# IEPE.net
KiCad netlist of a schematic drawn in Altium Designer
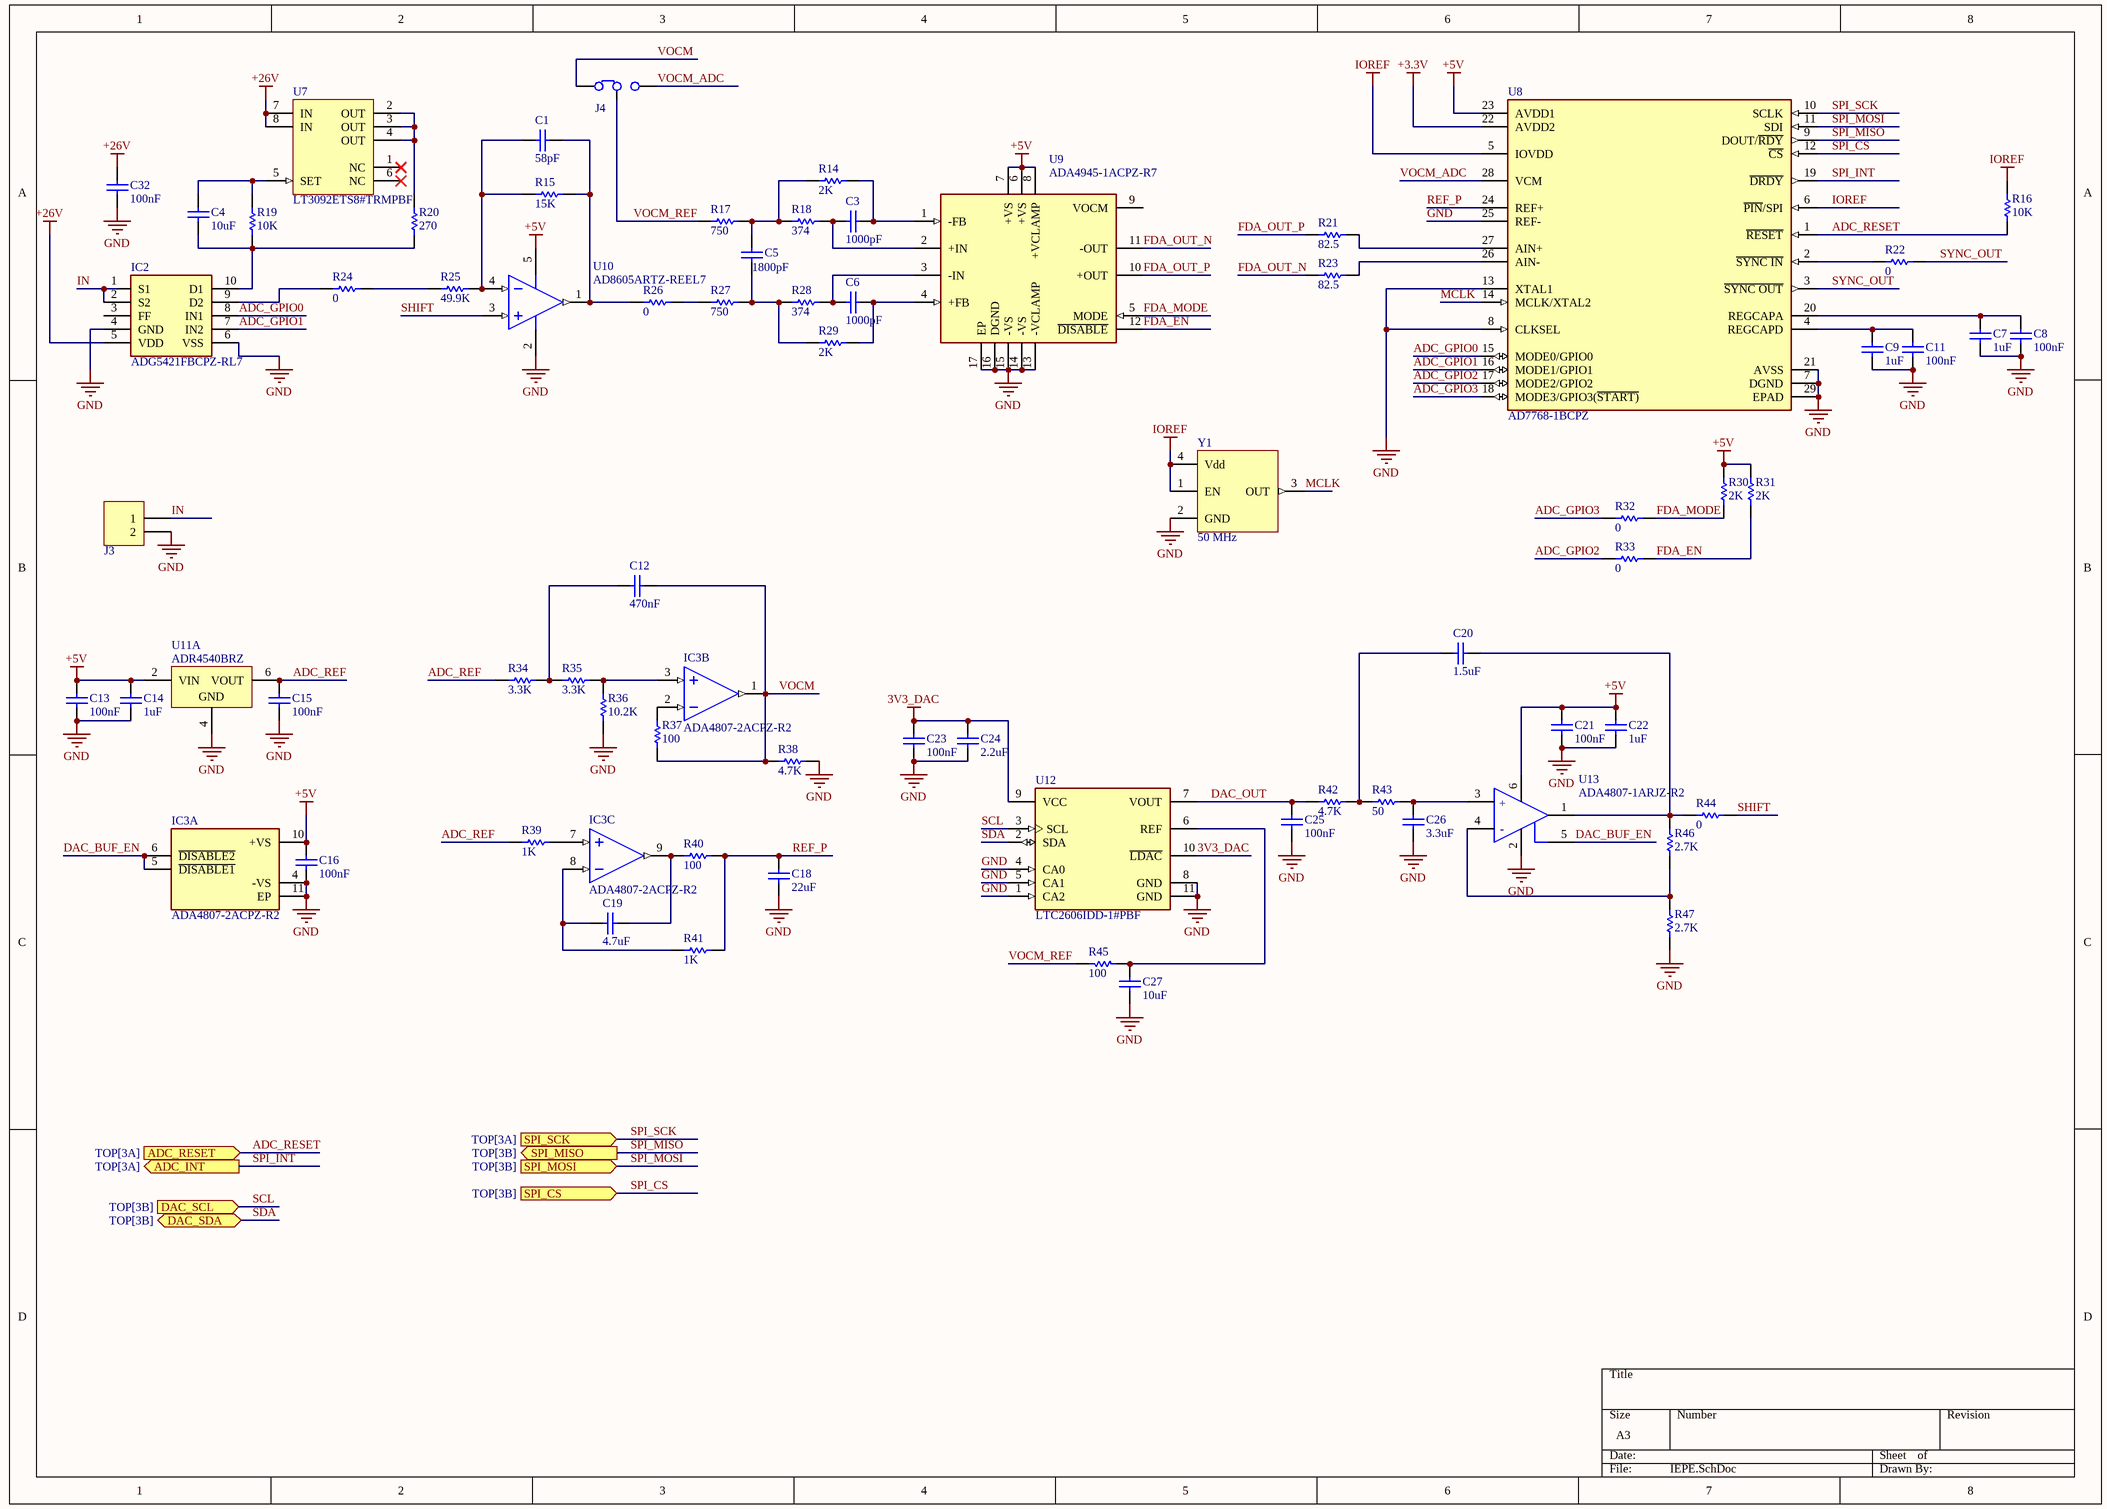
[diagram p0: IEPE.SchDoc]

(export (version "E")
  (design (tool "Eeschema 10.0.6"))
  (components
    (comp (ref "C1")
      (value "58pF")
      (footprint "C603")
      (description "Capacitor")
      (fields (field (name "DESIGNER") "Parsa Malekpour"))
      (libsource (lib "ParsaLibrary") (part "Cap"))
    )
    (comp (ref "C3")
      (value "1000pF")
      (footprint "C603")
      (description "Capacitor")
      (fields (field (name "DESIGNER") "Parsa Malekpour"))
      (libsource (lib "ParsaLibrary") (part "Cap"))
    )
    (comp (ref "C4")
      (value "10uF")
      (footprint "C805")
      (description "Capacitor")
      (fields (field (name "DESIGNER") "Parsa Malekpour"))
      (libsource (lib "ParsaLibrary") (part "Cap"))
    )
    (comp (ref "C5")
      (value "1800pF")
      (footprint "C603")
      (description "Capacitor")
      (fields (field (name "DESIGNER") "Parsa Malekpour"))
      (libsource (lib "ParsaLibrary") (part "Cap"))
    )
    (comp (ref "C6")
      (value "1000pF")
      (footprint "C603")
      (description "Capacitor")
      (fields (field (name "DESIGNER") "Parsa Malekpour"))
      (libsource (lib "ParsaLibrary") (part "Cap"))
    )
    (comp (ref "C7")
      (value "1uF")
      (footprint "C603")
      (description "Capacitor")
      (fields (field (name "DESIGNER") "Parsa Malekpour"))
      (libsource (lib "ParsaLibrary") (part "Cap"))
    )
    (comp (ref "C8")
      (value "100nF")
      (footprint "C603")
      (description "Capacitor")
      (fields (field (name "DESIGNER") "Parsa Malekpour"))
      (libsource (lib "ParsaLibrary") (part "Cap"))
    )
    (comp (ref "C9")
      (value "1uF")
      (footprint "C603")
      (description "Capacitor")
      (fields (field (name "DESIGNER") "Parsa Malekpour"))
      (libsource (lib "ParsaLibrary") (part "Cap"))
    )
    (comp (ref "C11")
      (value "100nF")
      (footprint "C603")
      (description "Capacitor")
      (fields (field (name "DESIGNER") "Parsa Malekpour"))
      (libsource (lib "ParsaLibrary") (part "Cap"))
    )
    (comp (ref "C12")
      (value "470nF")
      (footprint "C603")
      (description "Capacitor")
      (fields (field (name "DESIGNER") "Parsa Malekpour"))
      (libsource (lib "ParsaLibrary") (part "Cap"))
    )
    (comp (ref "C13")
      (value "100nF")
      (footprint "C603")
      (description "Capacitor")
      (fields (field (name "DESIGNER") "Parsa Malekpour"))
      (libsource (lib "ParsaLibrary") (part "Cap"))
    )
    (comp (ref "C14")
      (value "1uF")
      (footprint "C603")
      (description "Capacitor")
      (fields (field (name "DESIGNER") "Parsa Malekpour"))
      (libsource (lib "ParsaLibrary") (part "Cap"))
    )
    (comp (ref "C15")
      (value "100nF")
      (footprint "C603")
      (description "Capacitor")
      (fields (field (name "DESIGNER") "Parsa Malekpour"))
      (libsource (lib "ParsaLibrary") (part "Cap"))
    )
    (comp (ref "C16")
      (value "100nF")
      (footprint "C603")
      (description "Capacitor")
      (fields (field (name "DESIGNER") "Parsa Malekpour"))
      (libsource (lib "ParsaLibrary") (part "Cap"))
    )
    (comp (ref "C18")
      (value "22uF")
      (footprint "C603")
      (description "Capacitor")
      (fields (field (name "DESIGNER") "Parsa Malekpour"))
      (libsource (lib "ParsaLibrary") (part "Cap"))
    )
    (comp (ref "C19")
      (value "4.7uF")
      (footprint "C603")
      (description "Capacitor")
      (fields (field (name "DESIGNER") "Parsa Malekpour"))
      (libsource (lib "ParsaLibrary") (part "Cap"))
    )
    (comp (ref "C20")
      (value "1.5uF")
      (footprint "C603")
      (description "Capacitor")
      (fields (field (name "DESIGNER") "Parsa Malekpour"))
      (libsource (lib "ParsaLibrary") (part "Cap"))
    )
    (comp (ref "C21")
      (value "100nF")
      (footprint "C603")
      (description "Capacitor")
      (fields (field (name "DESIGNER") "Parsa Malekpour"))
      (libsource (lib "ParsaLibrary") (part "Cap"))
    )
    (comp (ref "C22")
      (value "1uF")
      (footprint "C603")
      (description "Capacitor")
      (fields (field (name "DESIGNER") "Parsa Malekpour"))
      (libsource (lib "ParsaLibrary") (part "Cap"))
    )
    (comp (ref "C23")
      (value "100nF")
      (footprint "C603")
      (description "Capacitor")
      (fields (field (name "DESIGNER") "Parsa Malekpour"))
      (libsource (lib "ParsaLibrary") (part "Cap"))
    )
    (comp (ref "C24")
      (value "2.2uF")
      (footprint "C603")
      (description "Capacitor")
      (fields (field (name "DESIGNER") "Parsa Malekpour"))
      (libsource (lib "ParsaLibrary") (part "Cap"))
    )
    (comp (ref "C25")
      (value "100nF")
      (footprint "C603")
      (description "Capacitor")
      (fields (field (name "DESIGNER") "Parsa Malekpour"))
      (libsource (lib "ParsaLibrary") (part "Cap"))
    )
    (comp (ref "C26")
      (value "3.3uF")
      (footprint "C603")
      (description "Capacitor")
      (fields (field (name "DESIGNER") "Parsa Malekpour"))
      (libsource (lib "ParsaLibrary") (part "Cap"))
    )
    (comp (ref "C27")
      (value "10uF")
      (footprint "C603")
      (description "Capacitor")
      (fields (field (name "DESIGNER") "Parsa Malekpour"))
      (libsource (lib "ParsaLibrary") (part "Cap"))
    )
    (comp (ref "C32")
      (value "100nF")
      (footprint "C603")
      (description "Capacitor")
      (fields (field (name "DESIGNER") "Parsa Malekpour"))
      (libsource (lib "ParsaLibrary") (part "Cap"))
    )
    (comp (ref "IC2")
      (value "ADG5421FBCPZ-RL7")
      (footprint "SamacSys:SON50P200X300X80-10N-D")
      (description "Integrated Circuit")
      (fields (field (name "MOUSER PART NUMBER") "584-ADG5421FBCPZ-RL7"))
      (libsource (lib "*") (part "ADG5421FBCPZ-RL7"))
    )
    (comp (ref "IC3")
      (value "ADA4807-2ACPZ-R2")
      (footprint "SON50P300X300X80-11N-D")
      (description "Integrated Circuit")
      (fields (field (name "MOUSER PART NUMBER") "584-ADA4807-2ACPZ-R2"))
      (libsource (lib "1") (part "ADA4807-2ACPZ-R2"))
    )
    (comp (ref "J3") (value "CONN-2") (footprint "SMB-ANT") (libsource (lib "ParsaLibrary") (part "CONN-2")))
    (comp (ref "J4")
      (value "jumper")
      (footprint "jumper-3-SMD")
      (description "Jumper wire")
      (libsource (lib "ParsaLibrary") (part "Triple Jumper"))
    )
    (comp (ref "R14")
      (value "2K")
      (footprint "R0603")
      (description "Resistor")
      (fields (field (name "DESIGNER") "Parsa Malekpour"))
      (libsource (lib "ParsaLibrary") (part "Resistor"))
    )
    (comp (ref "R15")
      (value "15K")
      (footprint "R0603")
      (description "Resistor")
      (fields (field (name "DESIGNER") "Parsa Malekpour"))
      (libsource (lib "ParsaLibrary") (part "Resistor"))
    )
    (comp (ref "R16")
      (value "10K")
      (footprint "R0603")
      (description "Resistor")
      (fields (field (name "DESIGNER") "Parsa Malekpour"))
      (libsource (lib "ParsaLibrary") (part "Resistor"))
    )
    (comp (ref "R17")
      (value "750")
      (footprint "R0603")
      (description "Resistor")
      (fields (field (name "DESIGNER") "Parsa Malekpour"))
      (libsource (lib "ParsaLibrary") (part "Resistor"))
    )
    (comp (ref "R18")
      (value "374")
      (footprint "R0603")
      (description "Resistor")
      (fields (field (name "DESIGNER") "Parsa Malekpour"))
      (libsource (lib "ParsaLibrary") (part "Resistor"))
    )
    (comp (ref "R19")
      (value "10K")
      (footprint "R0603")
      (description "Resistor")
      (fields (field (name "DESIGNER") "Parsa Malekpour"))
      (libsource (lib "ParsaLibrary") (part "Resistor"))
    )
    (comp (ref "R20")
      (value "270")
      (footprint "R0603")
      (description "Resistor")
      (fields (field (name "DESIGNER") "Parsa Malekpour"))
      (libsource (lib "ParsaLibrary") (part "Resistor"))
    )
    (comp (ref "R21")
      (value "82.5")
      (footprint "R0603")
      (description "Resistor")
      (fields (field (name "DESIGNER") "Parsa Malekpour"))
      (libsource (lib "ParsaLibrary") (part "Resistor"))
    )
    (comp (ref "R22")
      (value "0")
      (footprint "R0603")
      (description "Resistor")
      (fields (field (name "DESIGNER") "Parsa Malekpour"))
      (libsource (lib "ParsaLibrary") (part "Resistor"))
    )
    (comp (ref "R23")
      (value "82.5")
      (footprint "R0603")
      (description "Resistor")
      (fields (field (name "DESIGNER") "Parsa Malekpour"))
      (libsource (lib "ParsaLibrary") (part "Resistor"))
    )
    (comp (ref "R24")
      (value "0")
      (footprint "R0603")
      (description "Resistor")
      (fields (field (name "DESIGNER") "Parsa Malekpour"))
      (libsource (lib "ParsaLibrary") (part "Resistor"))
    )
    (comp (ref "R25")
      (value "49.9K")
      (footprint "R0603")
      (description "Resistor")
      (fields (field (name "DESIGNER") "Parsa Malekpour"))
      (libsource (lib "ParsaLibrary") (part "Resistor"))
    )
    (comp (ref "R26")
      (value "0")
      (footprint "R0603")
      (description "Resistor")
      (fields (field (name "DESIGNER") "Parsa Malekpour"))
      (libsource (lib "ParsaLibrary") (part "Resistor"))
    )
    (comp (ref "R27")
      (value "750")
      (footprint "R0603")
      (description "Resistor")
      (fields (field (name "DESIGNER") "Parsa Malekpour"))
      (libsource (lib "ParsaLibrary") (part "Resistor"))
    )
    (comp (ref "R28")
      (value "374")
      (footprint "R0603")
      (description "Resistor")
      (fields (field (name "DESIGNER") "Parsa Malekpour"))
      (libsource (lib "ParsaLibrary") (part "Resistor"))
    )
    (comp (ref "R29")
      (value "2K")
      (footprint "R0603")
      (description "Resistor")
      (fields (field (name "DESIGNER") "Parsa Malekpour"))
      (libsource (lib "ParsaLibrary") (part "Resistor"))
    )
    (comp (ref "R30")
      (value "2K")
      (footprint "R0603")
      (description "Resistor")
      (fields (field (name "DESIGNER") "Parsa Malekpour"))
      (libsource (lib "ParsaLibrary") (part "Resistor"))
    )
    (comp (ref "R31")
      (value "2K")
      (footprint "R0603")
      (description "Resistor")
      (fields (field (name "DESIGNER") "Parsa Malekpour"))
      (libsource (lib "ParsaLibrary") (part "Resistor"))
    )
    (comp (ref "R32")
      (value "0")
      (footprint "R0603")
      (description "Resistor")
      (fields (field (name "DESIGNER") "Parsa Malekpour"))
      (libsource (lib "ParsaLibrary") (part "Resistor"))
    )
    (comp (ref "R33")
      (value "0")
      (footprint "R0603")
      (description "Resistor")
      (fields (field (name "DESIGNER") "Parsa Malekpour"))
      (libsource (lib "ParsaLibrary") (part "Resistor"))
    )
    (comp (ref "R34")
      (value "3.3K")
      (footprint "R0603")
      (description "Resistor")
      (fields (field (name "DESIGNER") "Parsa Malekpour"))
      (libsource (lib "ParsaLibrary") (part "Resistor"))
    )
    (comp (ref "R35")
      (value "3.3K")
      (footprint "R0603")
      (description "Resistor")
      (fields (field (name "DESIGNER") "Parsa Malekpour"))
      (libsource (lib "ParsaLibrary") (part "Resistor"))
    )
    (comp (ref "R36")
      (value "10.2K")
      (footprint "R0603")
      (description "Resistor")
      (fields (field (name "DESIGNER") "Parsa Malekpour"))
      (libsource (lib "ParsaLibrary") (part "Resistor"))
    )
    (comp (ref "R37")
      (value "100")
      (footprint "R0603")
      (description "Resistor")
      (fields (field (name "DESIGNER") "Parsa Malekpour"))
      (libsource (lib "ParsaLibrary") (part "Resistor"))
    )
    (comp (ref "R38")
      (value "4.7K")
      (footprint "R0603")
      (description "Resistor")
      (fields (field (name "DESIGNER") "Parsa Malekpour"))
      (libsource (lib "ParsaLibrary") (part "Resistor"))
    )
    (comp (ref "R39")
      (value "1K")
      (footprint "R0603")
      (description "Resistor")
      (fields (field (name "DESIGNER") "Parsa Malekpour"))
      (libsource (lib "ParsaLibrary") (part "Resistor"))
    )
    (comp (ref "R40")
      (value "100")
      (footprint "R0603")
      (description "Resistor")
      (fields (field (name "DESIGNER") "Parsa Malekpour"))
      (libsource (lib "ParsaLibrary") (part "Resistor"))
    )
    (comp (ref "R41")
      (value "1K")
      (footprint "R0603")
      (description "Resistor")
      (fields (field (name "DESIGNER") "Parsa Malekpour"))
      (libsource (lib "ParsaLibrary") (part "Resistor"))
    )
    (comp (ref "R42")
      (value "4.7K")
      (footprint "R0603")
      (description "Resistor")
      (fields (field (name "DESIGNER") "Parsa Malekpour"))
      (libsource (lib "ParsaLibrary") (part "Resistor"))
    )
    (comp (ref "R43")
      (value "50")
      (footprint "R0603")
      (description "Resistor")
      (fields (field (name "DESIGNER") "Parsa Malekpour"))
      (libsource (lib "ParsaLibrary") (part "Resistor"))
    )
    (comp (ref "R44")
      (value "0")
      (footprint "R0603")
      (description "Resistor")
      (fields (field (name "DESIGNER") "Parsa Malekpour"))
      (libsource (lib "ParsaLibrary") (part "Resistor"))
    )
    (comp (ref "R45")
      (value "100")
      (footprint "R0603")
      (description "Resistor")
      (fields (field (name "DESIGNER") "Parsa Malekpour"))
      (libsource (lib "ParsaLibrary") (part "Resistor"))
    )
    (comp (ref "R46")
      (value "2.7K")
      (footprint "R0603")
      (description "Resistor")
      (fields (field (name "DESIGNER") "Parsa Malekpour"))
      (libsource (lib "ParsaLibrary") (part "Resistor"))
    )
    (comp (ref "R47")
      (value "2.7K")
      (footprint "R0603")
      (description "Resistor")
      (fields (field (name "DESIGNER") "Parsa Malekpour"))
      (libsource (lib "ParsaLibrary") (part "Resistor"))
    )
    (comp (ref "U7")
      (value "LT3092ETS8#TRMPBF")
      (footprint "SOT65P280X100-8N")
      (fields (field (name "MANUFACTURER") "Linear Technology"))
      (libsource (lib "SamacSys") (part "LT-LT3092-TS8-8"))
    )
    (comp (ref "U8")
      (value "AD7768-1BCPZ")
      (footprint "FP-CP-28-12-IPC_C")
      (description "IC ADC 24BIT SIGMA-DELTA 28LFCSP")
      (libsource (lib "Altium Content Vault") (part "6bcfa4bee2ba14552dcdb65def92038"))
    )
    (comp (ref "U9")
      (value "ADA4945-1ACPZ-R7")
      (footprint "FP-CP-16-22-IPC_C")
      (description "IC ADC DRIVER 16LFCSP")
      (libsource (lib "ParsaLibrary") (part "ADA4945-1ACPZ-R7"))
    )
    (comp (ref "U10")
      (value "AD8605ARTZ-REEL7")
      (footprint "SOT95P280X145-5N")
      (fields (field (name "MANUFACTURER") "Analog Devices") (field (name "GENERIC PART NUMBER") "AD8605"))
      (libsource (lib "SamacSys") (part "ADI-ADxxxx-X-5"))
    )
    (comp (ref "U11")
      (value "ADR4540BRZ")
      (footprint "SOIC-8N")
      (fields (field (name "MANUFACTURER") "Analog Devices"))
      (libsource (lib "SamacSys") (part "ADI-ADR45xx-R-8"))
    )
    (comp (ref "U12")
      (value "LTC2606IDD-1#PBF")
      (footprint "FP-DD-10-05-08-1699-IPC_C")
      (description "IC DAC 16BIT V-OUT 10DFN")
      (libsource (lib "Altium Content Vault") (part "0d41aa5bbc5989ae32548436e883e6b"))
    )
    (comp (ref "U13")
      (value "ADA4807-1ARJZ-R2")
      (footprint "FP-RJ-6-IPC_A")
      (description "IC OPAMP VFB 1 CIRCUIT SOT23-6")
      (libsource (lib "Altium Content Vault") (part "0cc169e61f44c0172c2773b4ba3b2c6"))
    )
    (comp (ref "Y1")
      (value "50 MHz")
      (footprint "OSC3225")
      (description "OSCILLATOR")
      (fields (field (name "FREQUENCY") "50 MHz"))
      (libsource (lib "ParsaLibrary") (part "OSCILLATOR"))
    )
  )
  (nets
    (net (code "1") (name "+3.3V") (class "Default")
      (node (ref "U8") (pin "22") (pinfunction "AVDD2_22") (pintype "power_in"))
    )
    (net (code "2") (name "+5V") (class "Default")
      (node (ref "C13") (pin "1") (pinfunction "1_1") (pintype "passive"))
      (node (ref "C14") (pin "1") (pinfunction "1_1") (pintype "passive"))
      (node (ref "C16") (pin "1") (pinfunction "1_1") (pintype "passive"))
      (node (ref "C21") (pin "1") (pinfunction "1_1") (pintype "passive"))
      (node (ref "C22") (pin "1") (pinfunction "1_1") (pintype "passive"))
      (node (ref "IC3") (pin "10") (pinfunction "+VS_10") (pintype "passive"))
      (node (ref "R30") (pin "1") (pinfunction "1_1") (pintype "passive"))
      (node (ref "R31") (pin "1") (pinfunction "1_1") (pintype "passive"))
      (node (ref "U10") (pin "5") (pinfunction "+V_5") (pintype "power_in"))
      (node (ref "U11") (pin "2") (pinfunction "VIN_2") (pintype "power_in"))
      (node (ref "U13") (pin "6") (pinfunction "+VS_6") (pintype "power_in"))
      (node (ref "U8") (pin "23") (pinfunction "AVDD1_23") (pintype "power_in"))
      (node (ref "U9") (pin "6") (pinfunction "+VS_6") (pintype "power_in"))
      (node (ref "U9") (pin "7") (pinfunction "+VS_7") (pintype "power_in"))
      (node (ref "U9") (pin "8") (pinfunction "+VCLAMP_8") (pintype "power_in"))
    )
    (net (code "3") (name "+26V") (class "Default")
      (node (ref "C32") (pin "1") (pinfunction "1_1") (pintype "passive"))
      (node (ref "IC2") (pin "5") (pinfunction "VDD_5") (pintype "passive"))
      (node (ref "U7") (pin "7") (pinfunction "IN_7") (pintype "power_in"))
      (node (ref "U7") (pin "8") (pinfunction "IN_8") (pintype "power_in"))
    )
    (net (code "4") (name "/ADC_GPIO0") (class "Default")
      (node (ref "IC2") (pin "8") (pinfunction "IN1_8") (pintype "passive"))
      (node (ref "U8") (pin "15") (pinfunction "MODE0/GPIO0_15") (pintype "bidirectional"))
    )
    (net (code "5") (name "/ADC_GPIO1") (class "Default")
      (node (ref "IC2") (pin "7") (pinfunction "IN2_7") (pintype "passive"))
      (node (ref "U8") (pin "16") (pinfunction "MODE1/GPIO1_16") (pintype "bidirectional"))
    )
    (net (code "6") (name "/ADC_GPIO2") (class "Default")
      (node (ref "R33") (pin "2") (pinfunction "2_2") (pintype "passive"))
      (node (ref "U8") (pin "17") (pinfunction "MODE2/GPIO2_17") (pintype "bidirectional"))
    )
    (net (code "7") (name "/ADC_GPIO3") (class "Default")
      (node (ref "R32") (pin "2") (pinfunction "2_2") (pintype "passive"))
      (node (ref "U8") (pin "18") (pinfunction "MODE3/GPIO3(~{START)}_18") (pintype "bidirectional"))
    )
    (net (code "8") (name "/ADC_REF") (class "Default")
      (node (ref "C15") (pin "1") (pinfunction "1_1") (pintype "passive"))
      (node (ref "R34") (pin "2") (pinfunction "2_2") (pintype "passive"))
      (node (ref "R39") (pin "1") (pinfunction "1_1") (pintype "passive"))
      (node (ref "U11") (pin "6") (pinfunction "VOUT_6") (pintype "power_in"))
    )
    (net (code "9") (name "/ADC_RESET") (class "Default")
      (node (ref "R16") (pin "2") (pinfunction "2_2") (pintype "passive"))
      (node (ref "U8") (pin "1") (pinfunction "~{RESET}_1") (pintype "input"))
    )
    (net (code "10") (name "/DAC_BUF_EN") (class "Default")
      (node (ref "IC3") (pin "5") (pinfunction "~{DISABLE1}_5") (pintype "passive"))
      (node (ref "IC3") (pin "6") (pinfunction "~{DISABLE2}_6") (pintype "passive"))
      (node (ref "U13") (pin "5") (pinfunction "~{DISABLE}_5") (pintype "passive"))
    )
    (net (code "11") (name "/DAC_OUT") (class "Default")
      (node (ref "C25") (pin "1") (pinfunction "1_1") (pintype "passive"))
      (node (ref "R42") (pin "1") (pinfunction "1_1") (pintype "passive"))
      (node (ref "U12") (pin "7") (pinfunction "VOUT_7") (pintype "passive"))
    )
    (net (code "12") (name "/FDA_EN") (class "Default")
      (node (ref "R31") (pin "2") (pinfunction "2_2") (pintype "passive"))
      (node (ref "R33") (pin "1") (pinfunction "1_1") (pintype "passive"))
      (node (ref "U9") (pin "12") (pinfunction "~{DISABLE}_12") (pintype "passive"))
    )
    (net (code "13") (name "/FDA_MODE") (class "Default")
      (node (ref "R30") (pin "2") (pinfunction "2_2") (pintype "passive"))
      (node (ref "R32") (pin "1") (pinfunction "1_1") (pintype "passive"))
      (node (ref "U9") (pin "5") (pinfunction "MODE_5") (pintype "input"))
    )
    (net (code "14") (name "/FDA_OUT_N") (class "Default")
      (node (ref "R23") (pin "2") (pinfunction "2_2") (pintype "passive"))
      (node (ref "U9") (pin "11") (pinfunction "-OUT_11") (pintype "passive"))
    )
    (net (code "15") (name "/FDA_OUT_P") (class "Default")
      (node (ref "R21") (pin "2") (pinfunction "2_2") (pintype "passive"))
      (node (ref "U9") (pin "10") (pinfunction "+OUT_10") (pintype "passive"))
    )
    (net (code "16") (name "/IN") (class "Default")
      (node (ref "IC2") (pin "1") (pinfunction "S1_1") (pintype "passive"))
      (node (ref "IC2") (pin "2") (pinfunction "S2_2") (pintype "passive"))
      (node (ref "J3") (pin "1") (pinfunction "1_1") (pintype "passive"))
    )
    (net (code "17") (name "/MCLK") (class "Default")
      (node (ref "U8") (pin "14") (pinfunction "MCLK/XTAL2_14") (pintype "input"))
      (node (ref "Y1") (pin "3") (pinfunction "OUT_3") (pintype "output"))
    )
    (net (code "18") (name "/REF_P") (class "Default")
      (node (ref "C18") (pin "1") (pinfunction "1_1") (pintype "passive"))
      (node (ref "R40") (pin "2") (pinfunction "2_2") (pintype "passive"))
      (node (ref "R41") (pin "2") (pinfunction "2_2") (pintype "passive"))
      (node (ref "U8") (pin "24") (pinfunction "REF+_24") (pintype "passive"))
    )
    (net (code "19") (name "/SCL") (class "Default")
      (node (ref "U12") (pin "3") (pinfunction "SCL_3") (pintype "input"))
    )
    (net (code "20") (name "/SDA") (class "Default")
      (node (ref "U12") (pin "2") (pinfunction "SDA_2") (pintype "bidirectional"))
    )
    (net (code "21") (name "/SHIFT") (class "Default")
      (node (ref "R44") (pin "2") (pinfunction "2_2") (pintype "passive"))
      (node (ref "U10") (pin "3") (pinfunction "+IN_3") (pintype "input"))
    )
    (net (code "22") (name "/SPI_CS") (class "Default")
      (node (ref "U8") (pin "12") (pinfunction "~{CS}_12") (pintype "input"))
    )
    (net (code "23") (name "/SPI_INT") (class "Default")
      (node (ref "U8") (pin "19") (pinfunction "~{DRDY}_19") (pintype "output"))
    )
    (net (code "24") (name "/SPI_MISO") (class "Default")
      (node (ref "U8") (pin "9") (pinfunction "DOUT/~{RDY}_9") (pintype "output"))
    )
    (net (code "25") (name "/SPI_MOSI") (class "Default")
      (node (ref "U8") (pin "11") (pinfunction "SDI_11") (pintype "input"))
    )
    (net (code "26") (name "/SPI_SCK") (class "Default")
      (node (ref "U8") (pin "10") (pinfunction "SCLK_10") (pintype "input"))
    )
    (net (code "27") (name "/SYNC_OUT") (class "Default")
      (node (ref "R22") (pin "1") (pinfunction "1_1") (pintype "passive"))
      (node (ref "U8") (pin "3") (pinfunction "~{SYNC_OUT}_3") (pintype "output"))
    )
    (net (code "28") (name "/VOCM") (class "Default")
      (node (ref "C12") (pin "1") (pinfunction "1_1") (pintype "passive"))
      (node (ref "IC3") (pin "1") (pinfunction "VOUT_1") (pintype "output"))
      (node (ref "J4") (pin "1") (pinfunction "C1_1") (pintype "passive"))
      (node (ref "R37") (pin "2") (pinfunction "2_2") (pintype "passive"))
      (node (ref "R38") (pin "1") (pinfunction "1_1") (pintype "passive"))
    )
    (net (code "29") (name "/VOCM_ADC") (class "Default")
      (node (ref "J4") (pin "3") (pinfunction "C3_3") (pintype "passive"))
      (node (ref "U8") (pin "28") (pinfunction "VCM_28") (pintype "passive"))
    )
    (net (code "30") (name "/VOCM_REF") (class "Default")
      (node (ref "J4") (pin "2") (pinfunction "C2_2") (pintype "passive"))
      (node (ref "R17") (pin "2") (pinfunction "2_2") (pintype "passive"))
      (node (ref "R45") (pin "2") (pinfunction "2_2") (pintype "passive"))
    )
    (net (code "31") (name "3V3_DAC") (class "Default")
      (node (ref "C23") (pin "1") (pinfunction "1_1") (pintype "passive"))
      (node (ref "C24") (pin "1") (pinfunction "1_1") (pintype "passive"))
      (node (ref "U12") (pin "10") (pinfunction "~{LDAC}_10") (pintype "passive"))
      (node (ref "U12") (pin "9") (pinfunction "VCC_9") (pintype "power_in"))
    )
    (net (code "32") (name "GND") (class "Default")
      (node (ref "C11") (pin "2") (pinfunction "2_2") (pintype "passive"))
      (node (ref "C13") (pin "2") (pinfunction "2_2") (pintype "passive"))
      (node (ref "C14") (pin "2") (pinfunction "2_2") (pintype "passive"))
      (node (ref "C15") (pin "2") (pinfunction "2_2") (pintype "passive"))
      (node (ref "C16") (pin "2") (pinfunction "2_2") (pintype "passive"))
      (node (ref "C18") (pin "2") (pinfunction "2_2") (pintype "passive"))
      (node (ref "C21") (pin "2") (pinfunction "2_2") (pintype "passive"))
      (node (ref "C22") (pin "2") (pinfunction "2_2") (pintype "passive"))
      (node (ref "C23") (pin "2") (pinfunction "2_2") (pintype "passive"))
      (node (ref "C24") (pin "2") (pinfunction "2_2") (pintype "passive"))
      (node (ref "C25") (pin "2") (pinfunction "2_2") (pintype "passive"))
      (node (ref "C26") (pin "2") (pinfunction "2_2") (pintype "passive"))
      (node (ref "C27") (pin "2") (pinfunction "2_2") (pintype "passive"))
      (node (ref "C32") (pin "2") (pinfunction "2_2") (pintype "passive"))
      (node (ref "C7") (pin "2") (pinfunction "2_2") (pintype "passive"))
      (node (ref "C8") (pin "2") (pinfunction "2_2") (pintype "passive"))
      (node (ref "C9") (pin "2") (pinfunction "2_2") (pintype "passive"))
      (node (ref "IC2") (pin "4") (pinfunction "GND_4") (pintype "passive"))
      (node (ref "IC2") (pin "6") (pinfunction "VSS_6") (pintype "passive"))
      (node (ref "IC3") (pin "11") (pinfunction "EP_11") (pintype "passive"))
      (node (ref "IC3") (pin "4") (pinfunction "-VS_4") (pintype "passive"))
      (node (ref "J3") (pin "2") (pinfunction "2_2") (pintype "passive"))
      (node (ref "R36") (pin "2") (pinfunction "2_2") (pintype "passive"))
      (node (ref "R38") (pin "2") (pinfunction "2_2") (pintype "passive"))
      (node (ref "R47") (pin "1") (pinfunction "1_1") (pintype "passive"))
      (node (ref "U10") (pin "2") (pinfunction "-V_2") (pintype "power_in"))
      (node (ref "U11") (pin "4") (pinfunction "GND_4") (pintype "power_in"))
      (node (ref "U12") (pin "1") (pinfunction "CA2_1") (pintype "input"))
      (node (ref "U12") (pin "11") (pinfunction "GND_11") (pintype "power_in"))
      (node (ref "U12") (pin "4") (pinfunction "CA0_4") (pintype "input"))
      (node (ref "U12") (pin "5") (pinfunction "CA1_5") (pintype "input"))
      (node (ref "U12") (pin "8") (pinfunction "GND_8") (pintype "power_in"))
      (node (ref "U13") (pin "2") (pinfunction "-VS_2") (pintype "power_in"))
      (node (ref "U8") (pin "13") (pinfunction "XTAL1_13") (pintype "passive"))
      (node (ref "U8") (pin "21") (pinfunction "AVSS_21") (pintype "power_in"))
      (node (ref "U8") (pin "25") (pinfunction "REF-_25") (pintype "passive"))
      (node (ref "U8") (pin "29") (pinfunction "EPAD_29") (pintype "power_in"))
      (node (ref "U8") (pin "7") (pinfunction "DGND_7") (pintype "power_in"))
      (node (ref "U8") (pin "8") (pinfunction "CLKSEL_8") (pintype "input"))
      (node (ref "U9") (pin "13") (pinfunction "-VCLAMP_13") (pintype "power_in"))
      (node (ref "U9") (pin "14") (pinfunction "-VS_14") (pintype "power_in"))
      (node (ref "U9") (pin "15") (pinfunction "-VS_15") (pintype "power_in"))
      (node (ref "U9") (pin "16") (pinfunction "DGND_16") (pintype "power_in"))
      (node (ref "U9") (pin "17") (pinfunction "EP_17") (pintype "passive"))
      (node (ref "Y1") (pin "2") (pinfunction "GND_2") (pintype "passive"))
    )
    (net (code "33") (name "IOREF") (class "Default")
      (node (ref "R16") (pin "1") (pinfunction "1_1") (pintype "passive"))
      (node (ref "U8") (pin "5") (pinfunction "IOVDD_5") (pintype "power_in"))
      (node (ref "U8") (pin "6") (pinfunction "~{PIN}/SPI_6") (pintype "input"))
      (node (ref "Y1") (pin "1") (pinfunction "EN_1") (pintype "passive"))
      (node (ref "Y1") (pin "4") (pinfunction "Vdd_4") (pintype "passive"))
    )
    (net (code "34") (name "Net-(C5-Pad1)") (class "Default")
      (node (ref "C5") (pin "1") (pinfunction "1_1") (pintype "passive"))
      (node (ref "R14") (pin "2") (pinfunction "2_2") (pintype "passive"))
      (node (ref "R17") (pin "1") (pinfunction "1_1") (pintype "passive"))
      (node (ref "R18") (pin "2") (pinfunction "2_2") (pintype "passive"))
    )
    (net (code "35") (name "Net-(C5-Pad2)") (class "Default")
      (node (ref "C5") (pin "2") (pinfunction "2_2") (pintype "passive"))
      (node (ref "R27") (pin "1") (pinfunction "1_1") (pintype "passive"))
      (node (ref "R28") (pin "2") (pinfunction "2_2") (pintype "passive"))
      (node (ref "R29") (pin "2") (pinfunction "2_2") (pintype "passive"))
    )
    (net (code "36") (name "Net-(C12-Pad2)") (class "Default")
      (node (ref "C12") (pin "2") (pinfunction "2_2") (pintype "passive"))
      (node (ref "R34") (pin "1") (pinfunction "1_1") (pintype "passive"))
      (node (ref "R35") (pin "2") (pinfunction "2_2") (pintype "passive"))
    )
    (net (code "37") (name "Net-(C20-Pad1)") (class "Default")
      (node (ref "C20") (pin "1") (pinfunction "1_1") (pintype "passive"))
      (node (ref "R42") (pin "2") (pinfunction "2_2") (pintype "passive"))
      (node (ref "R43") (pin "1") (pinfunction "1_1") (pintype "passive"))
    )
    (net (code "38") (name "Net-(IC2-D1)") (class "Default")
      (node (ref "C4") (pin "1") (pinfunction "1_1") (pintype "passive"))
      (node (ref "IC2") (pin "10") (pinfunction "D1_10") (pintype "passive"))
      (node (ref "R19") (pin "1") (pinfunction "1_1") (pintype "passive"))
      (node (ref "R20") (pin "1") (pinfunction "1_1") (pintype "passive"))
    )
    (net (code "39") (name "Net-(IC2-D2)") (class "Default")
      (node (ref "IC2") (pin "9") (pinfunction "D2_9") (pintype "passive"))
      (node (ref "R24") (pin "2") (pinfunction "2_2") (pintype "passive"))
    )
    (net (code "40") (name "Net-(IC3B-+IN1)") (class "Default")
      (node (ref "IC3") (pin "3") (pinfunction "+IN1_3") (pintype "input"))
      (node (ref "R35") (pin "1") (pinfunction "1_1") (pintype "passive"))
      (node (ref "R36") (pin "1") (pinfunction "1_1") (pintype "passive"))
    )
    (net (code "41") (name "Net-(IC3B--IN1)") (class "Default")
      (node (ref "IC3") (pin "2") (pinfunction "-IN1_2") (pintype "input"))
      (node (ref "R37") (pin "1") (pinfunction "1_1") (pintype "passive"))
    )
    (net (code "42") (name "Net-(IC3C-+IN2)") (class "Default")
      (node (ref "IC3") (pin "7") (pinfunction "+IN2_7") (pintype "input"))
      (node (ref "R39") (pin "2") (pinfunction "2_2") (pintype "passive"))
    )
    (net (code "43") (name "Net-(IC3C--IN2)") (class "Default")
      (node (ref "C19") (pin "2") (pinfunction "2_2") (pintype "passive"))
      (node (ref "IC3") (pin "8") (pinfunction "-IN2_8") (pintype "input"))
      (node (ref "R41") (pin "1") (pinfunction "1_1") (pintype "passive"))
    )
    (net (code "44") (name "Net-(IC3C-VOUT2)") (class "Default")
      (node (ref "C19") (pin "1") (pinfunction "1_1") (pintype "passive"))
      (node (ref "IC3") (pin "9") (pinfunction "VOUT2_9") (pintype "output"))
      (node (ref "R40") (pin "1") (pinfunction "1_1") (pintype "passive"))
    )
    (net (code "45") (name "Net-(R20-Pad2)") (class "Default")
      (node (ref "R20") (pin "2") (pinfunction "2_2") (pintype "passive"))
      (node (ref "U7") (pin "2") (pinfunction "OUT_2") (pintype "power_in"))
      (node (ref "U7") (pin "3") (pinfunction "OUT_3") (pintype "power_in"))
      (node (ref "U7") (pin "4") (pinfunction "OUT_4") (pintype "power_in"))
    )
    (net (code "46") (name "Net-(R24-Pad1)") (class "Default")
      (node (ref "R24") (pin "1") (pinfunction "1_1") (pintype "passive"))
      (node (ref "R25") (pin "2") (pinfunction "2_2") (pintype "passive"))
    )
    (net (code "47") (name "Net-(R26-Pad1)") (class "Default")
      (node (ref "R26") (pin "1") (pinfunction "1_1") (pintype "passive"))
      (node (ref "R27") (pin "2") (pinfunction "2_2") (pintype "passive"))
    )
    (net (code "48") (name "Net-(U7-SET)") (class "Default")
      (node (ref "C4") (pin "2") (pinfunction "2_2") (pintype "passive"))
      (node (ref "R19") (pin "2") (pinfunction "2_2") (pintype "passive"))
      (node (ref "U7") (pin "5") (pinfunction "SET_5") (pintype "input"))
    )
    (net (code "49") (name "Net-(U8-AIN+)") (class "Default")
      (node (ref "R21") (pin "1") (pinfunction "1_1") (pintype "passive"))
      (node (ref "U8") (pin "27") (pinfunction "AIN+_27") (pintype "passive"))
    )
    (net (code "50") (name "Net-(U8-AIN-)") (class "Default")
      (node (ref "R23") (pin "1") (pinfunction "1_1") (pintype "passive"))
      (node (ref "U8") (pin "26") (pinfunction "AIN-_26") (pintype "passive"))
    )
    (net (code "51") (name "Net-(U8-REGCAPA)") (class "Default")
      (node (ref "C7") (pin "1") (pinfunction "1_1") (pintype "passive"))
      (node (ref "C8") (pin "1") (pinfunction "1_1") (pintype "passive"))
      (node (ref "U8") (pin "20") (pinfunction "REGCAPA_20") (pintype "passive"))
    )
    (net (code "52") (name "Net-(U8-REGCAPD)") (class "Default")
      (node (ref "C11") (pin "1") (pinfunction "1_1") (pintype "passive"))
      (node (ref "C9") (pin "1") (pinfunction "1_1") (pintype "passive"))
      (node (ref "U8") (pin "4") (pinfunction "REGCAPD_4") (pintype "passive"))
    )
    (net (code "53") (name "Net-(U8-~{SYNC_IN})") (class "Default")
      (node (ref "R22") (pin "2") (pinfunction "2_2") (pintype "passive"))
      (node (ref "U8") (pin "2") (pinfunction "~{SYNC_IN}_2") (pintype "input"))
    )
    (net (code "54") (name "Net-(U9-+FB)") (class "Default")
      (node (ref "C6") (pin "2") (pinfunction "2_2") (pintype "passive"))
      (node (ref "R29") (pin "1") (pinfunction "1_1") (pintype "passive"))
      (node (ref "U9") (pin "4") (pinfunction "+FB_4") (pintype "input"))
    )
    (net (code "55") (name "Net-(U9-+IN)") (class "Default")
      (node (ref "C3") (pin "1") (pinfunction "1_1") (pintype "passive"))
      (node (ref "R18") (pin "1") (pinfunction "1_1") (pintype "passive"))
      (node (ref "U9") (pin "2") (pinfunction "+IN_2") (pintype "power_in"))
    )
    (net (code "56") (name "Net-(U9--FB)") (class "Default")
      (node (ref "C3") (pin "2") (pinfunction "2_2") (pintype "passive"))
      (node (ref "R14") (pin "1") (pinfunction "1_1") (pintype "passive"))
      (node (ref "U9") (pin "1") (pinfunction "-FB_1") (pintype "input"))
    )
    (net (code "57") (name "Net-(U9--IN)") (class "Default")
      (node (ref "C6") (pin "1") (pinfunction "1_1") (pintype "passive"))
      (node (ref "R28") (pin "1") (pinfunction "1_1") (pintype "passive"))
      (node (ref "U9") (pin "3") (pinfunction "-IN_3") (pintype "power_in"))
    )
    (net (code "58") (name "Net-(U10--IN)") (class "Default")
      (node (ref "C1") (pin "2") (pinfunction "2_2") (pintype "passive"))
      (node (ref "R15") (pin "2") (pinfunction "2_2") (pintype "passive"))
      (node (ref "R25") (pin "1") (pinfunction "1_1") (pintype "passive"))
      (node (ref "U10") (pin "4") (pinfunction "-IN_4") (pintype "input"))
    )
    (net (code "59") (name "Net-(U10-OUT)") (class "Default")
      (node (ref "C1") (pin "1") (pinfunction "1_1") (pintype "passive"))
      (node (ref "R15") (pin "1") (pinfunction "1_1") (pintype "passive"))
      (node (ref "R26") (pin "2") (pinfunction "2_2") (pintype "passive"))
      (node (ref "U10") (pin "1") (pinfunction "OUT_1") (pintype "output"))
    )
    (net (code "60") (name "Net-(U12-REF)") (class "Default")
      (node (ref "C27") (pin "1") (pinfunction "1_1") (pintype "passive"))
      (node (ref "R45") (pin "1") (pinfunction "1_1") (pintype "passive"))
      (node (ref "U12") (pin "6") (pinfunction "REF_6") (pintype "passive"))
    )
    (net (code "61") (name "Net-(U13-+IN)") (class "Default")
      (node (ref "C26") (pin "1") (pinfunction "1_1") (pintype "passive"))
      (node (ref "R43") (pin "2") (pinfunction "2_2") (pintype "passive"))
      (node (ref "U13") (pin "3") (pinfunction "+IN_3") (pintype "tri_state"))
    )
    (net (code "62") (name "Net-(U13--IN)") (class "Default")
      (node (ref "R46") (pin "1") (pinfunction "1_1") (pintype "passive"))
      (node (ref "R47") (pin "2") (pinfunction "2_2") (pintype "passive"))
      (node (ref "U13") (pin "4") (pinfunction "-IN_4") (pintype "tri_state"))
    )
    (net (code "63") (name "Net-(U13-VOUT)") (class "Default")
      (node (ref "C20") (pin "2") (pinfunction "2_2") (pintype "passive"))
      (node (ref "R44") (pin "1") (pinfunction "1_1") (pintype "passive"))
      (node (ref "R46") (pin "2") (pinfunction "2_2") (pintype "passive"))
      (node (ref "U13") (pin "1") (pinfunction "VOUT_1") (pintype "passive"))
    )
    (net (code "64") (name "unconnected-(IC2-FF-Pad3)") (class "Default")
      (node (ref "IC2") (pin "3") (pinfunction "FF_3") (pintype "passive"))
    )
    (net (code "65") (name "unconnected-(U7-NC-Pad1)") (class "Default")
      (node (ref "U7") (pin "1") (pinfunction "NC_1") (pintype "passive+no_connect"))
    )
    (net (code "66") (name "unconnected-(U7-NC-Pad6)") (class "Default")
      (node (ref "U7") (pin "6") (pinfunction "NC_6") (pintype "passive+no_connect"))
    )
    (net (code "67") (name "unconnected-(U9-VOCM-Pad9)") (class "Default")
      (node (ref "U9") (pin "9") (pinfunction "VOCM_9") (pintype "power_in"))
    )
  )
)
